# simonSaysModule.net
KiCad netlist of a schematic drawn in EAGLE
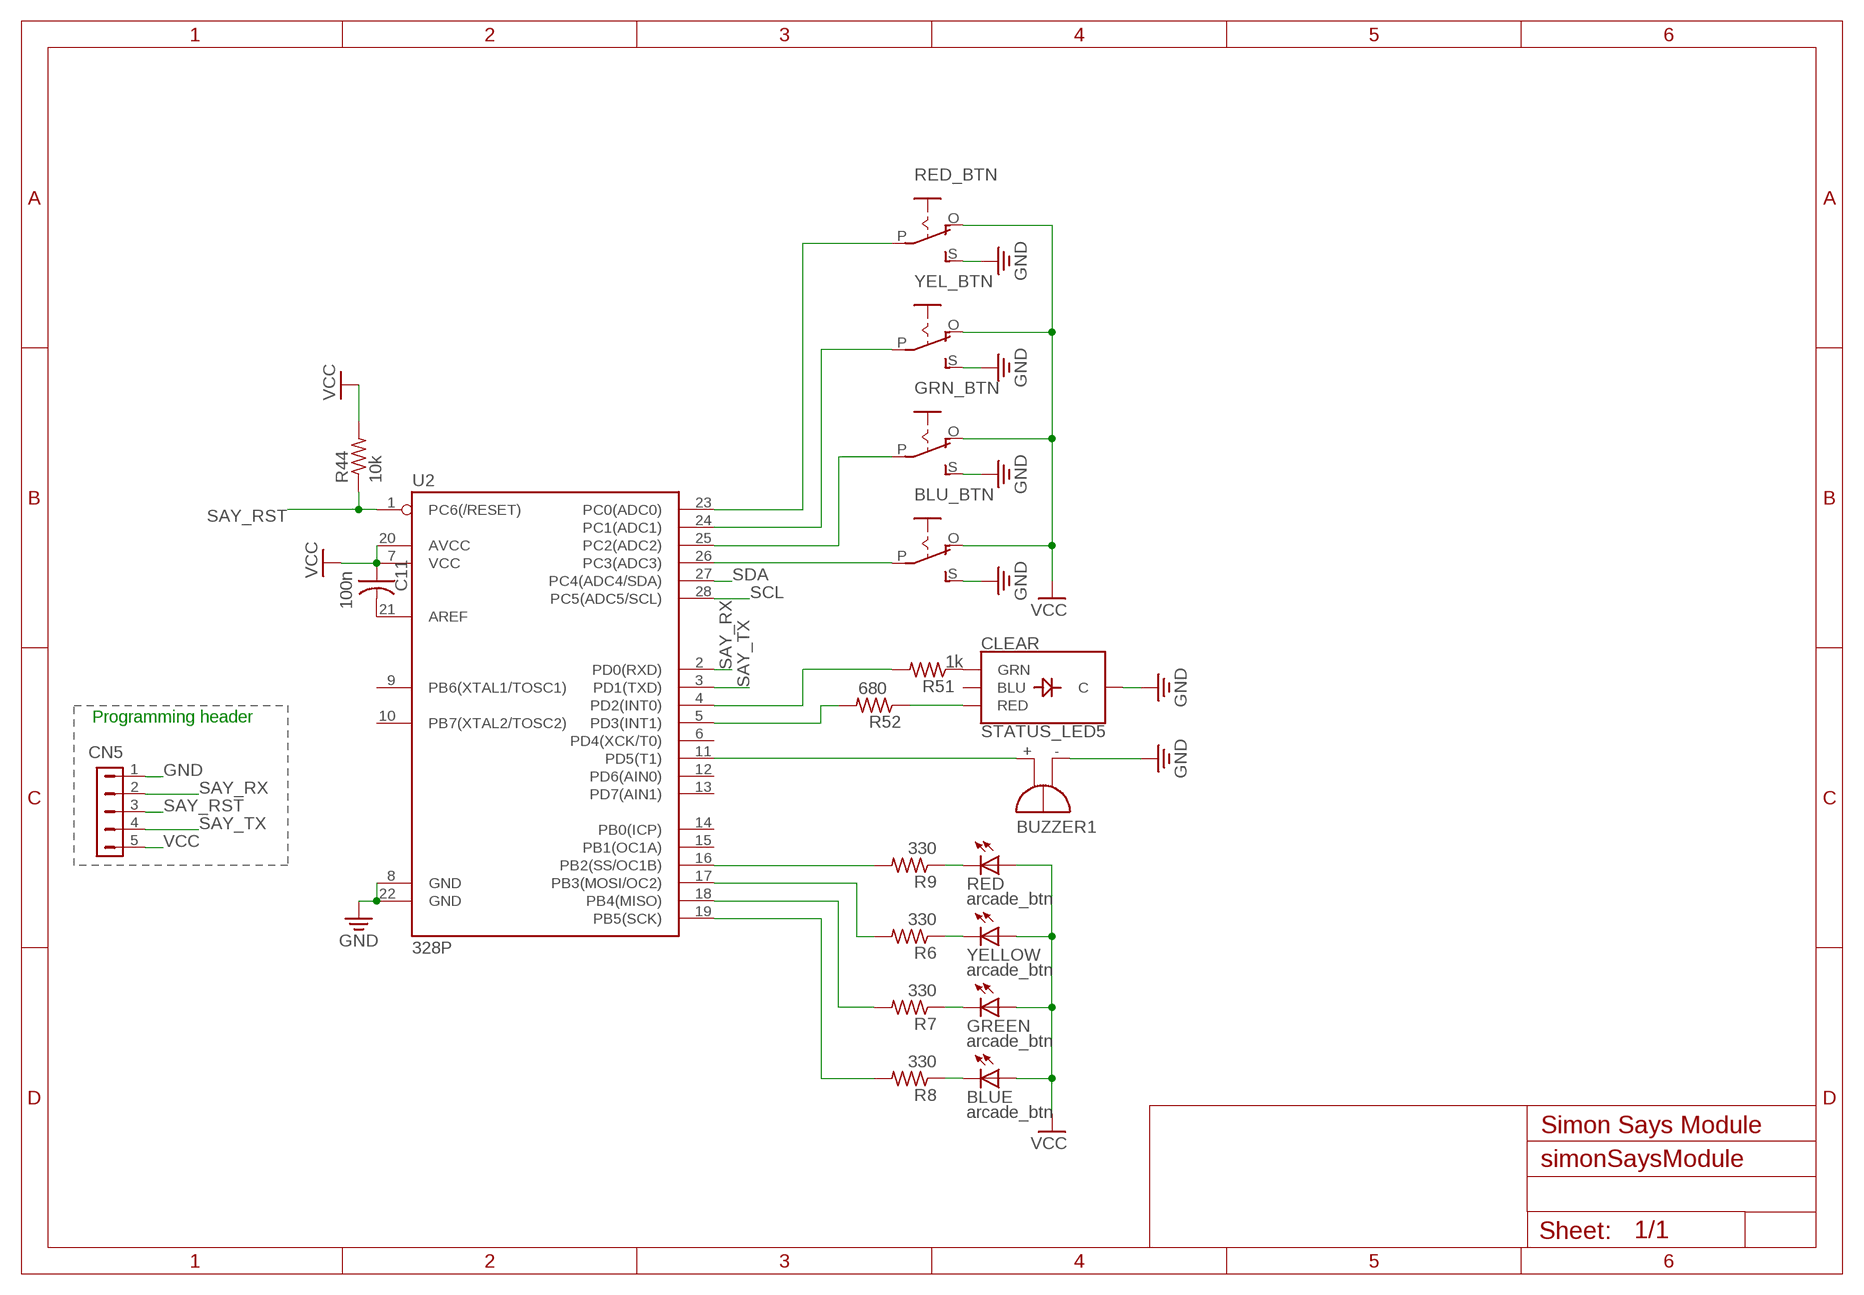
[diagram p0: schematic, sheet 1]

(export (version "E")
  (design (tool "Eeschema 10.0.6"))
  (components
    (comp (ref "BLUE")
      (value "arcade_btn")
      (footprint "eagle-import:LED5MM")
      (libsource (lib "eagle-import") (part "LED5MM"))
    )
    (comp (ref "BLU_BTN")
      (value "EG1218S")
      (footprint "eagle-import:EG1218")
      (libsource (lib "eagle-import") (part "EG1218S"))
    )
    (comp (ref "BUZZER1")
      (value "EB2209A")
      (footprint "eagle-import:EB2209A")
      (libsource (lib "eagle-import") (part "EB2209A"))
    )
    (comp (ref "C11")
      (value "100n")
      (footprint "eagle-import:C025-024X044")
      (libsource (lib "eagle-import") (part "C-US025-024X044"))
    )
    (comp (ref "CN5")
      (value "HDR-1X5-SIP-100")
      (footprint "eagle-import:SIP-100-5V")
      (libsource (lib "eagle-import") (part "HDR-1X5-SIP-100"))
    )
    (comp (ref "GREEN")
      (value "arcade_btn")
      (footprint "eagle-import:LED5MM")
      (libsource (lib "eagle-import") (part "LED5MM"))
    )
    (comp (ref "GRN_BTN")
      (value "EG1218S")
      (footprint "eagle-import:EG1218")
      (libsource (lib "eagle-import") (part "EG1218S"))
    )
    (comp (ref "R6")
      (value "330")
      (footprint "eagle-import:0309_12")
      (libsource (lib "eagle-import") (part "R-US_0309/12"))
    )
    (comp (ref "R7")
      (value "330")
      (footprint "eagle-import:0309_12")
      (libsource (lib "eagle-import") (part "R-US_0309/12"))
    )
    (comp (ref "R8")
      (value "330")
      (footprint "eagle-import:0309_12")
      (libsource (lib "eagle-import") (part "R-US_0309/12"))
    )
    (comp (ref "R9")
      (value "330")
      (footprint "eagle-import:0309_12")
      (libsource (lib "eagle-import") (part "R-US_0309/12"))
    )
    (comp (ref "R44")
      (value "10k")
      (footprint "eagle-import:0309_12")
      (libsource (lib "eagle-import") (part "R-US_0309/12"))
    )
    (comp (ref "R51")
      (value "1k")
      (footprint "eagle-import:0805-THM")
      (libsource (lib "eagle-import") (part "FLIPFLOP-RES"))
    )
    (comp (ref "R52")
      (value "680")
      (footprint "eagle-import:0805-THM")
      (libsource (lib "eagle-import") (part "FLIPFLOP-RES"))
    )
    (comp (ref "RED")
      (value "arcade_btn")
      (footprint "eagle-import:LED5MM")
      (libsource (lib "eagle-import") (part "LED5MM"))
    )
    (comp (ref "RED_BTN")
      (value "EG1218S")
      (footprint "eagle-import:EG1218")
      (libsource (lib "eagle-import") (part "EG1218S"))
    )
    (comp (ref "STATUS_LED5")
      (value "CLEAR")
      (footprint "eagle-import:LED-RGB-THRU")
      (libsource (lib "eagle-import") (part "LED-RGB-CCCLEAR"))
    )
    (comp (ref "U2")
      (value "328P")
      (footprint "eagle-import:DIP28")
      (libsource (lib "eagle-import") (part "ATMEGA328P_PDIP"))
    )
    (comp (ref "YELLOW")
      (value "arcade_btn")
      (footprint "eagle-import:LED5MM")
      (libsource (lib "eagle-import") (part "LED5MM"))
    )
    (comp (ref "YEL_BTN")
      (value "EG1218S")
      (footprint "eagle-import:EG1218")
      (libsource (lib "eagle-import") (part "EG1218S"))
    )
  )
  (nets
    (net (code "1") (name "/N$48") (class "Default")
      (node (ref "R7") (pin "2") (pinfunction "2_2") (pintype "passive"))
      (node (ref "R8") (pin "2") (pinfunction "2_2") (pintype "passive"))
      (node (ref "U2") (pin "18") (pinfunction "PB4(MISO)_18") (pintype "bidirectional"))
      (node (ref "U2") (pin "19") (pinfunction "PB5(SCK)_19") (pintype "bidirectional"))
    )
    (net (code "2") (name "/SAY_RST") (class "Default")
      (node (ref "CN5") (pin "3") (pinfunction "3_3") (pintype "passive"))
      (node (ref "R44") (pin "1") (pinfunction "1_1") (pintype "passive"))
      (node (ref "U2") (pin "1") (pinfunction "PC6(/RESET)_1") (pintype "bidirectional"))
    )
    (net (code "3") (name "/SAY_RX") (class "Default")
      (node (ref "CN5") (pin "2") (pinfunction "2_2") (pintype "passive"))
      (node (ref "U2") (pin "2") (pinfunction "PD0(RXD)_2") (pintype "bidirectional"))
    )
    (net (code "4") (name "/SAY_TX") (class "Default")
      (node (ref "CN5") (pin "4") (pinfunction "4_4") (pintype "passive"))
      (node (ref "U2") (pin "3") (pinfunction "PD1(TXD)_3") (pintype "bidirectional"))
    )
    (net (code "5") (name "/SCL") (class "Default")
      (node (ref "U2") (pin "28") (pinfunction "PC5(ADC5/SCL)_28") (pintype "bidirectional"))
    )
    (net (code "6") (name "/SDA") (class "Default")
      (node (ref "U2") (pin "27") (pinfunction "PC4(ADC4/SDA)_27") (pintype "bidirectional"))
    )
    (net (code "7") (name "GND") (class "Default")
      (node (ref "BLU_BTN") (pin "S") (pinfunction "S_S") (pintype "passive"))
      (node (ref "BUZZER1") (pin "-") (pinfunction "-_-") (pintype "passive"))
      (node (ref "CN5") (pin "1") (pinfunction "1_1") (pintype "passive"))
      (node (ref "GRN_BTN") (pin "S") (pinfunction "S_S") (pintype "passive"))
      (node (ref "RED_BTN") (pin "S") (pinfunction "S_S") (pintype "passive"))
      (node (ref "STATUS_LED5") (pin "2") (pinfunction "C_2") (pintype "bidirectional"))
      (node (ref "U2") (pin "22") (pinfunction "GND_22") (pintype "bidirectional"))
      (node (ref "U2") (pin "8") (pinfunction "GND_8") (pintype "bidirectional"))
      (node (ref "YEL_BTN") (pin "S") (pinfunction "S_S") (pintype "passive"))
    )
    (net (code "8") (name "Net-(BLUE-C)") (class "Default")
      (node (ref "BLUE") (pin "K") (pinfunction "C_K") (pintype "passive"))
      (node (ref "R8") (pin "1") (pinfunction "1_1") (pintype "passive"))
    )
    (net (code "9") (name "Net-(GREEN-C)") (class "Default")
      (node (ref "GREEN") (pin "K") (pinfunction "C_K") (pintype "passive"))
      (node (ref "R7") (pin "1") (pinfunction "1_1") (pintype "passive"))
    )
    (net (code "10") (name "Net-(RED-C)") (class "Default")
      (node (ref "R9") (pin "1") (pinfunction "1_1") (pintype "passive"))
      (node (ref "RED") (pin "K") (pinfunction "C_K") (pintype "passive"))
    )
    (net (code "11") (name "Net-(STATUS_LED5-GRN)") (class "Default")
      (node (ref "R51") (pin "1") (pinfunction "1_1") (pintype "passive"))
      (node (ref "STATUS_LED5") (pin "3") (pinfunction "GRN_3") (pintype "bidirectional"))
    )
    (net (code "12") (name "Net-(STATUS_LED5-RED)") (class "Default")
      (node (ref "R52") (pin "1") (pinfunction "1_1") (pintype "passive"))
      (node (ref "STATUS_LED5") (pin "1") (pinfunction "RED_1") (pintype "bidirectional"))
    )
    (net (code "13") (name "Net-(U2-AREF)") (class "Default")
      (node (ref "C11") (pin "2") (pinfunction "2_2") (pintype "passive"))
      (node (ref "U2") (pin "21") (pinfunction "AREF_21") (pintype "bidirectional"))
    )
    (net (code "14") (name "Net-(U2-PB2(SS{slash}OC1B))") (class "Default")
      (node (ref "R9") (pin "2") (pinfunction "2_2") (pintype "passive"))
      (node (ref "U2") (pin "16") (pinfunction "PB2(SS/OC1B)_16") (pintype "bidirectional"))
    )
    (net (code "15") (name "Net-(U2-PB3(MOSI{slash}OC2))") (class "Default")
      (node (ref "R6") (pin "2") (pinfunction "2_2") (pintype "passive"))
      (node (ref "U2") (pin "17") (pinfunction "PB3(MOSI/OC2)_17") (pintype "bidirectional"))
    )
    (net (code "16") (name "Net-(U2-PC0(ADC0))") (class "Default")
      (node (ref "RED_BTN") (pin "P") (pinfunction "P_P") (pintype "passive"))
      (node (ref "U2") (pin "23") (pinfunction "PC0(ADC0)_23") (pintype "bidirectional"))
    )
    (net (code "17") (name "Net-(U2-PC1(ADC1))") (class "Default")
      (node (ref "U2") (pin "24") (pinfunction "PC1(ADC1)_24") (pintype "bidirectional"))
      (node (ref "YEL_BTN") (pin "P") (pinfunction "P_P") (pintype "passive"))
    )
    (net (code "18") (name "Net-(U2-PC2(ADC2))") (class "Default")
      (node (ref "GRN_BTN") (pin "P") (pinfunction "P_P") (pintype "passive"))
      (node (ref "U2") (pin "25") (pinfunction "PC2(ADC2)_25") (pintype "bidirectional"))
    )
    (net (code "19") (name "Net-(U2-PC3(ADC3))") (class "Default")
      (node (ref "BLU_BTN") (pin "P") (pinfunction "P_P") (pintype "passive"))
      (node (ref "U2") (pin "26") (pinfunction "PC3(ADC3)_26") (pintype "bidirectional"))
    )
    (net (code "20") (name "Net-(U2-PD2(INT0))") (class "Default")
      (node (ref "R51") (pin "2") (pinfunction "2_2") (pintype "passive"))
      (node (ref "U2") (pin "4") (pinfunction "PD2(INT0)_4") (pintype "bidirectional"))
    )
    (net (code "21") (name "Net-(U2-PD3(INT1))") (class "Default")
      (node (ref "R52") (pin "2") (pinfunction "2_2") (pintype "passive"))
      (node (ref "U2") (pin "5") (pinfunction "PD3(INT1)_5") (pintype "bidirectional"))
    )
    (net (code "22") (name "Net-(U2-PD5(T1))") (class "Default")
      (node (ref "BUZZER1") (pin "+") (pinfunction "+_+") (pintype "passive"))
      (node (ref "U2") (pin "11") (pinfunction "PD5(T1)_11") (pintype "bidirectional"))
    )
    (net (code "23") (name "Net-(YELLOW-C)") (class "Default")
      (node (ref "R6") (pin "1") (pinfunction "1_1") (pintype "passive"))
      (node (ref "YELLOW") (pin "K") (pinfunction "C_K") (pintype "passive"))
    )
    (net (code "24") (name "VCC") (class "Default")
      (node (ref "BLUE") (pin "A") (pinfunction "A_A") (pintype "passive"))
      (node (ref "BLU_BTN") (pin "O") (pinfunction "O_O") (pintype "passive"))
      (node (ref "C11") (pin "1") (pinfunction "1_1") (pintype "passive"))
      (node (ref "CN5") (pin "5") (pinfunction "5_5") (pintype "passive"))
      (node (ref "GREEN") (pin "A") (pinfunction "A_A") (pintype "passive"))
      (node (ref "GRN_BTN") (pin "O") (pinfunction "O_O") (pintype "passive"))
      (node (ref "R44") (pin "2") (pinfunction "2_2") (pintype "passive"))
      (node (ref "RED") (pin "A") (pinfunction "A_A") (pintype "passive"))
      (node (ref "RED_BTN") (pin "O") (pinfunction "O_O") (pintype "passive"))
      (node (ref "U2") (pin "20") (pinfunction "AVCC_20") (pintype "bidirectional"))
      (node (ref "U2") (pin "7") (pinfunction "VCC_7") (pintype "bidirectional"))
      (node (ref "YELLOW") (pin "A") (pinfunction "A_A") (pintype "passive"))
      (node (ref "YEL_BTN") (pin "O") (pinfunction "O_O") (pintype "passive"))
    )
    (net (code "25") (name "unconnected-(STATUS_LED5-BLU-Pad4)") (class "Default")
      (node (ref "STATUS_LED5") (pin "4") (pinfunction "BLU_4") (pintype "bidirectional"))
    )
    (net (code "26") (name "unconnected-(U2-PB0(ICP)-Pad14)") (class "Default")
      (node (ref "U2") (pin "14") (pinfunction "PB0(ICP)_14") (pintype "bidirectional"))
    )
    (net (code "27") (name "unconnected-(U2-PB1(OC1A)-Pad15)") (class "Default")
      (node (ref "U2") (pin "15") (pinfunction "PB1(OC1A)_15") (pintype "bidirectional"))
    )
    (net (code "28") (name "unconnected-(U2-PB6(XTAL1{slash}TOSC1)-Pad9)") (class "Default")
      (node (ref "U2") (pin "9") (pinfunction "PB6(XTAL1/TOSC1)_9") (pintype "bidirectional"))
    )
    (net (code "29") (name "unconnected-(U2-PB7(XTAL2{slash}TOSC2)-Pad10)") (class "Default")
      (node (ref "U2") (pin "10") (pinfunction "PB7(XTAL2/TOSC2)_10") (pintype "bidirectional"))
    )
    (net (code "30") (name "unconnected-(U2-PD4(XCK{slash}T0)-Pad6)") (class "Default")
      (node (ref "U2") (pin "6") (pinfunction "PD4(XCK/T0)_6") (pintype "bidirectional"))
    )
    (net (code "31") (name "unconnected-(U2-PD6(AIN0)-Pad12)") (class "Default")
      (node (ref "U2") (pin "12") (pinfunction "PD6(AIN0)_12") (pintype "bidirectional"))
    )
    (net (code "32") (name "unconnected-(U2-PD7(AIN1)-Pad13)") (class "Default")
      (node (ref "U2") (pin "13") (pinfunction "PD7(AIN1)_13") (pintype "bidirectional"))
    )
  )
)
